# 07_uart.net
KiCad netlist of a schematic drawn in Altium Designer
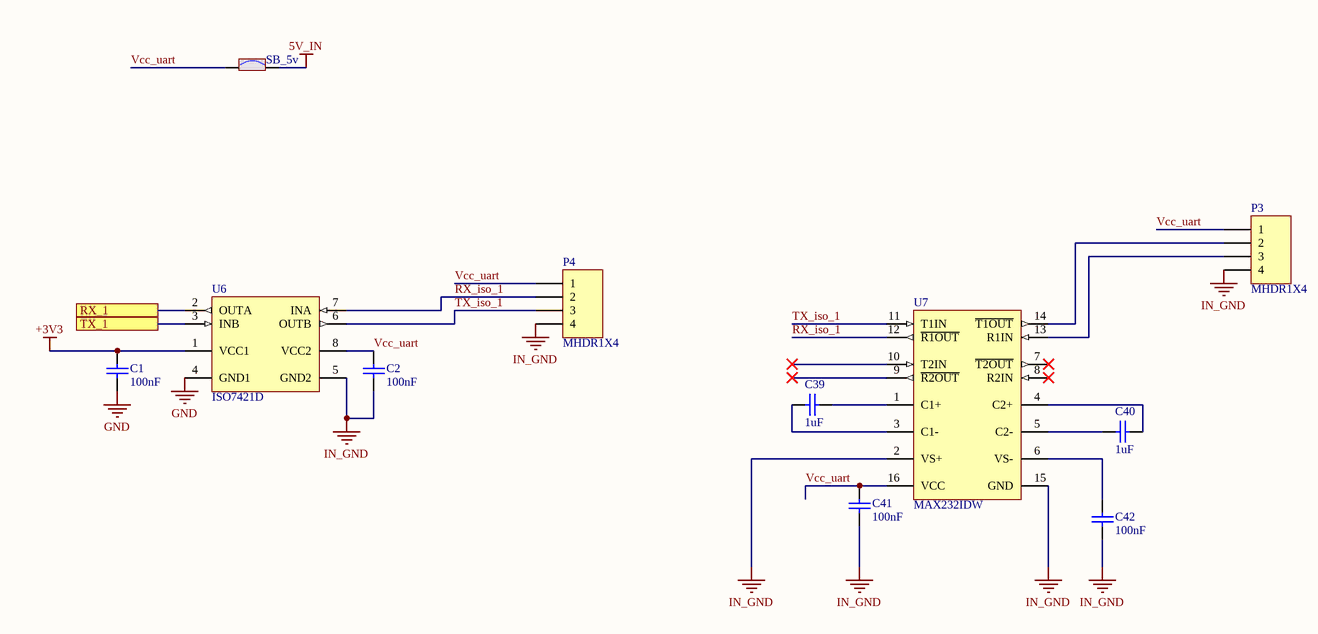
[diagram p0: 07_uart.SchDoc]

(export (version "E")
  (design (tool "Eeschema 10.0.6"))
  (components
    (comp (ref "C1")
      (value "100nF")
      (footprint "C0603")
      (description "Capacitor, MLCC, 100nF, 16V, X7R, 10%, 0402, T=0,5mm")
      (fields
        (field (name "INTERNAL_PART_NUMBER") "MCD-00102")
        (field (name "MANUFACTURER_PART_NUMBER") "CC0402KRX7R7BB104")
        (field (name "PROVIDED_BY") "SUBCO")
      )
      (libsource (lib "MCD_PARTS_database") (part "Capacitor"))
    )
    (comp (ref "C2")
      (value "100nF")
      (footprint "C0603")
      (description "Capacitor, MLCC, 100nF, 16V, X7R, 10%, 0402, T=0,5mm")
      (fields
        (field (name "INTERNAL_PART_NUMBER") "MCD-00102")
        (field (name "MANUFACTURER_PART_NUMBER") "CC0402KRX7R7BB104")
        (field (name "PROVIDED_BY") "SUBCO")
      )
      (libsource (lib "MCD_PARTS_database") (part "Capacitor"))
    )
    (comp (ref "C39")
      (value "1uF")
      (footprint "C0603")
      (description "Capacitor, MLCC, 1µF, 10V, X5R, 20%, 0603, T=0,8mm")
      (fields
        (field (name "INTERNAL_PART_NUMBER") "MCD-01121")
        (field (name "MANUFACTURER_PART_NUMBER") "GRM188R61A475ME15")
        (field (name "PROVIDED_BY") "Subcon")
      )
      (libsource (lib "MCD_PARTS_database") (part "Capacitor"))
    )
    (comp (ref "C40")
      (value "1uF")
      (footprint "C0603")
      (description "Capacitor, MLCC, 1µF, 10V, X5R, 20%, 0603, T=0,8mm")
      (fields
        (field (name "INTERNAL_PART_NUMBER") "MCD-01121")
        (field (name "MANUFACTURER_PART_NUMBER") "GRM188R61A475ME15")
        (field (name "PROVIDED_BY") "Subcon")
      )
      (libsource (lib "MCD_PARTS_database") (part "Capacitor"))
    )
    (comp (ref "C41")
      (value "100nF")
      (footprint "C0603")
      (description "Capacitor, MLCC, 100nF, 16V, X5R, 10%, 0603, T=0,8mm")
      (fields
        (field (name "INTERNAL_PART_NUMBER") "MCD-00010")
        (field (name "MANUFACTURER_PART_NUMBER") "CC0603KRX5R7BB105")
        (field (name "PROVIDED_BY") "SUBCO")
      )
      (libsource (lib "MCD_PARTS_database") (part "Capacitor"))
    )
    (comp (ref "C42")
      (value "100nF")
      (footprint "C0603")
      (description "Capacitor, MLCC, 100nF, 16V, X5R, 10%, 0603, T=0,8mm")
      (fields
        (field (name "INTERNAL_PART_NUMBER") "MCD-00010")
        (field (name "MANUFACTURER_PART_NUMBER") "CC0603KRX5R7BB105")
        (field (name "PROVIDED_BY") "SUBCO")
      )
      (libsource (lib "MCD_PARTS_database") (part "Capacitor"))
    )
    (comp (ref "P3")
      (value "MHDR1X4")
      (footprint "MHDR1X4")
      (description "Header, 4-Pin")
      (fields (field (name "PUBLISHER") "Altium Limited"))
      (libsource (lib "Miscellaneous Connectors") (part "MHDR1X4"))
    )
    (comp (ref "P4")
      (value "MHDR1X4")
      (footprint "MHDR1X4")
      (description "Header, 4-Pin")
      (fields (field (name "PUBLISHER") "Altium Limited"))
      (libsource (lib "Miscellaneous Connectors") (part "MHDR1X4"))
    )
    (comp (ref "SB_5v")
      (value "~")
      (footprint "SOLDER-BRIDGE_R0603-0R")
      (description "Solder Bridge ON")
      (fields (field (name "INTERNAL_PART_NUMBER") "MCD-00071") (field (name "PROVIDED_BY") "Subcon"))
      (libsource (lib "MCD_PARTS_database") (part "SB_ON"))
    )
    (comp (ref "U6")
      (value "ISO7421D")
      (footprint "D0008A_N")
      (fields (field (name "MANUFACTURER") "Texas Instruments"))
      (libsource (lib "TI Interface Isolator") (part "ISO7421D"))
    )
    (comp (ref "U7")
      (value "MAX232IDW")
      (footprint "TI-DW16_N")
      (description "Dual EIA-232 Driver / Receiver, -40 to 85 degC, 16-Pin SOIC (DW), Green (RoHS & no Sb/Br)")
      (libsource (lib "Texas Instruments Interface RS-232") (part "MAX232IDW"))
    )
  )
  (nets
    (net (code "1") (name "+3V3") (class "Default")
      (node (ref "C1") (pin "2") (pinfunction "2_2") (pintype "passive"))
      (node (ref "U6") (pin "1") (pinfunction "VCC1_1") (pintype "power_in"))
    )
    (net (code "2") (name "/RX_1") (class "Default")
      (node (ref "U6") (pin "2") (pinfunction "OUTA_2") (pintype "output"))
    )
    (net (code "3") (name "/RX_iso_1") (class "Default")
      (node (ref "P4") (pin "2") (pinfunction "2_2") (pintype "passive"))
      (node (ref "U6") (pin "7") (pinfunction "INA_7") (pintype "input"))
      (node (ref "U7") (pin "12") (pinfunction "~{R1OUT}_12") (pintype "output"))
    )
    (net (code "4") (name "/TX_1") (class "Default")
      (node (ref "U6") (pin "3") (pinfunction "INB_3") (pintype "input"))
    )
    (net (code "5") (name "/TX_iso_1") (class "Default")
      (node (ref "P4") (pin "3") (pinfunction "3_3") (pintype "passive"))
      (node (ref "U6") (pin "6") (pinfunction "OUTB_6") (pintype "output"))
      (node (ref "U7") (pin "11") (pinfunction "T1IN_11") (pintype "input"))
    )
    (net (code "6") (name "/Vcc_uart") (class "Default")
      (node (ref "C2") (pin "2") (pinfunction "2_2") (pintype "passive"))
      (node (ref "C41") (pin "2") (pinfunction "2_2") (pintype "passive"))
      (node (ref "P3") (pin "1") (pinfunction "1_1") (pintype "passive"))
      (node (ref "P4") (pin "1") (pinfunction "1_1") (pintype "passive"))
      (node (ref "SB_5v") (pin "1") (pinfunction "1_1") (pintype "passive"))
      (node (ref "U6") (pin "8") (pinfunction "VCC2_8") (pintype "power_in"))
      (node (ref "U7") (pin "16") (pinfunction "VCC_16") (pintype "power_in"))
    )
    (net (code "7") (name "5V_IN") (class "Default")
      (node (ref "SB_5v") (pin "2") (pinfunction "2_2") (pintype "passive"))
    )
    (net (code "8") (name "GND") (class "Default")
      (node (ref "C1") (pin "1") (pinfunction "1_1") (pintype "passive"))
      (node (ref "U6") (pin "4") (pinfunction "GND1_4") (pintype "power_in"))
    )
    (net (code "9") (name "IN_GND") (class "Default")
      (node (ref "C2") (pin "1") (pinfunction "1_1") (pintype "passive"))
      (node (ref "C41") (pin "1") (pinfunction "1_1") (pintype "passive"))
      (node (ref "C42") (pin "1") (pinfunction "1_1") (pintype "passive"))
      (node (ref "P3") (pin "4") (pinfunction "4_4") (pintype "passive"))
      (node (ref "P4") (pin "4") (pinfunction "4_4") (pintype "passive"))
      (node (ref "U6") (pin "5") (pinfunction "GND2_5") (pintype "power_in"))
      (node (ref "U7") (pin "15") (pinfunction "GND_15") (pintype "power_in"))
      (node (ref "U7") (pin "2") (pinfunction "VS+_2") (pintype "power_in"))
    )
    (net (code "10") (name "Net-(U7-C1+)") (class "Default")
      (node (ref "C39") (pin "1") (pinfunction "1_1") (pintype "passive"))
      (node (ref "U7") (pin "1") (pinfunction "C1+_1") (pintype "passive"))
    )
    (net (code "11") (name "Net-(U7-C1-)") (class "Default")
      (node (ref "C39") (pin "2") (pinfunction "2_2") (pintype "passive"))
      (node (ref "U7") (pin "3") (pinfunction "C1-_3") (pintype "passive"))
    )
    (net (code "12") (name "Net-(U7-C2+)") (class "Default")
      (node (ref "C40") (pin "2") (pinfunction "2_2") (pintype "passive"))
      (node (ref "U7") (pin "4") (pinfunction "C2+_4") (pintype "passive"))
    )
    (net (code "13") (name "Net-(U7-C2-)") (class "Default")
      (node (ref "C40") (pin "1") (pinfunction "1_1") (pintype "passive"))
      (node (ref "U7") (pin "5") (pinfunction "C2-_5") (pintype "passive"))
    )
    (net (code "14") (name "Net-(U7-R1IN)") (class "Default")
      (node (ref "P3") (pin "3") (pinfunction "3_3") (pintype "passive"))
      (node (ref "U7") (pin "13") (pinfunction "R1IN_13") (pintype "input"))
    )
    (net (code "15") (name "Net-(U7-VS-)") (class "Default")
      (node (ref "C42") (pin "2") (pinfunction "2_2") (pintype "passive"))
      (node (ref "U7") (pin "6") (pinfunction "VS-_6") (pintype "power_in"))
    )
    (net (code "16") (name "Net-(U7-~{T1OUT})") (class "Default")
      (node (ref "P3") (pin "2") (pinfunction "2_2") (pintype "passive"))
      (node (ref "U7") (pin "14") (pinfunction "~{T1OUT}_14") (pintype "output"))
    )
    (net (code "17") (name "unconnected-(U7-R2IN-Pad8)") (class "Default")
      (node (ref "U7") (pin "8") (pinfunction "R2IN_8") (pintype "input+no_connect"))
    )
    (net (code "18") (name "unconnected-(U7-T2IN-Pad10)") (class "Default")
      (node (ref "U7") (pin "10") (pinfunction "T2IN_10") (pintype "input+no_connect"))
    )
    (net (code "19") (name "unconnected-(U7-~{R2OUT}-Pad9)") (class "Default")
      (node (ref "U7") (pin "9") (pinfunction "~{R2OUT}_9") (pintype "output+no_connect"))
    )
    (net (code "20") (name "unconnected-(U7-~{T2OUT}-Pad7)") (class "Default")
      (node (ref "U7") (pin "7") (pinfunction "~{T2OUT}_7") (pintype "output+no_connect"))
    )
  )
)
